# v1_0_Sensor.net
KiCad netlist of a schematic drawn in EAGLE
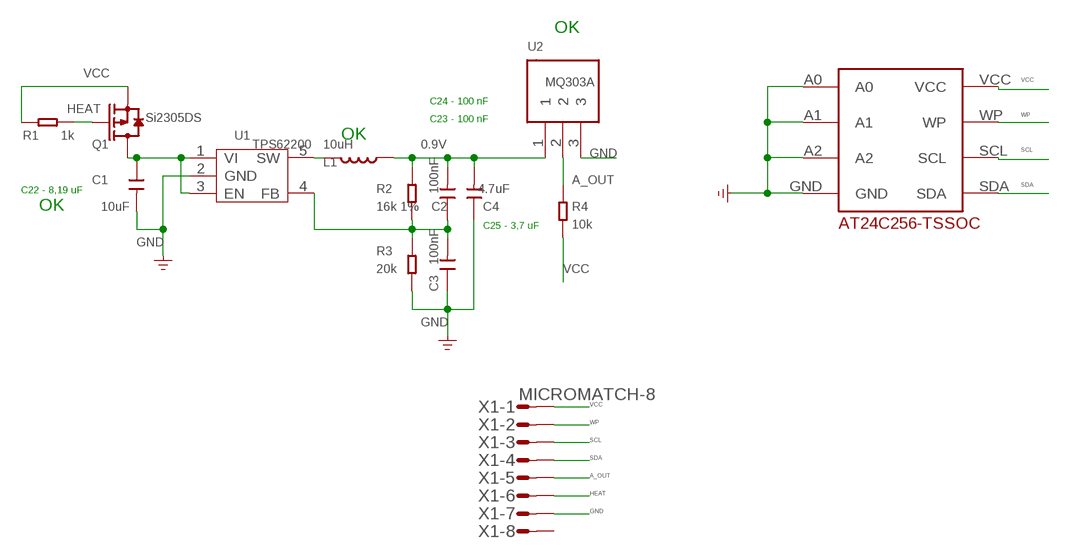
[diagram p0: schematic, sheet 1]

(export (version "E")
  (design (tool "Eeschema 10.0.6"))
  (components
    (comp (ref "C1")
      (value "10uF")
      (footprint "eagle-import:C0805")
      (libsource (lib "eagle-import") (part "C-0805"))
    )
    (comp (ref "C2")
      (value "100nF")
      (footprint "eagle-import:C0603")
      (libsource (lib "eagle-import") (part "C-0603"))
    )
    (comp (ref "C3")
      (value "100nF")
      (footprint "eagle-import:C0603")
      (libsource (lib "eagle-import") (part "C-0603"))
    )
    (comp (ref "C4")
      (value "4.7uF")
      (footprint "eagle-import:C0805")
      (libsource (lib "eagle-import") (part "C-0805"))
    )
    (comp (ref "L1")
      (value "10uH")
      (footprint "eagle-import:PIO73")
      (libsource (lib "eagle-import") (part "L'PIO73'"))
    )
    (comp (ref "Q1")
      (value "Si2305DS")
      (footprint "eagle-import:SOT23")
      (libsource (lib "eagle-import") (part "MOSFET-P'SI2323CDS/SI2305DS{lt}BR{gt}'"))
    )
    (comp (ref "R1")
      (value "1k")
      (footprint "eagle-import:R0603")
      (libsource (lib "eagle-import") (part "R-0603"))
    )
    (comp (ref "R2")
      (value "16k 1%")
      (footprint "eagle-import:R0603")
      (libsource (lib "eagle-import") (part "R-0603"))
    )
    (comp (ref "R3")
      (value "20k")
      (footprint "eagle-import:R0603")
      (libsource (lib "eagle-import") (part "R-0603"))
    )
    (comp (ref "R4")
      (value "10k")
      (footprint "eagle-import:R0603")
      (libsource (lib "eagle-import") (part "R-0603"))
    )
    (comp (ref "U$1")
      (value "DECADE-AT24C256-10TI-2.7")
      (footprint "eagle-import:DECADE-AT24CXX")
      (libsource (lib "eagle-import") (part "DECADE-AT24C256-10TI-2.7"))
    )
    (comp (ref "U1")
      (value "TPS62200")
      (footprint "eagle-import:SOT23-5")
      (libsource (lib "eagle-import") (part "TPS62200DBV"))
    )
    (comp (ref "U2")
      (value "MQ303A")
      (footprint "eagle-import:MQ303A")
      (libsource (lib "eagle-import") (part "MQ303A"))
    )
    (comp (ref "X1")
      (value "MICROMATCH-8")
      (footprint "eagle-import:MICROMATCH-8")
      (fields (field (name "MF") "FARNELL") (field (name "MPN") "7-215464-8"))
      (libsource (lib "eagle-import") (part "MICROMATCH-8"))
    )
  )
  (nets
    (net (code "1") (name "/0.9V") (class "Default")
      (node (ref "C2") (pin "2") (pinfunction "2_2") (pintype "passive"))
      (node (ref "C4") (pin "2") (pinfunction "2_2") (pintype "passive"))
      (node (ref "L1") (pin "2") (pinfunction "2_2") (pintype "passive"))
      (node (ref "R2") (pin "1") (pinfunction "1_1") (pintype "passive"))
      (node (ref "U2") (pin "1") (pinfunction "1_1") (pintype "bidirectional"))
    )
    (net (code "2") (name "/A_OUT") (class "Default")
      (node (ref "R4") (pin "1") (pinfunction "1_1") (pintype "passive"))
      (node (ref "U2") (pin "2") (pinfunction "2_2") (pintype "bidirectional"))
      (node (ref "X1") (pin "5") (pinfunction "S_5") (pintype "passive"))
    )
    (net (code "3") (name "/HEAT") (class "Default")
      (node (ref "Q1") (pin "1") (pinfunction "G_1") (pintype "passive"))
      (node (ref "R1") (pin "1") (pinfunction "1_1") (pintype "passive"))
      (node (ref "X1") (pin "6") (pinfunction "S_6") (pintype "passive"))
    )
    (net (code "4") (name "/SCL") (class "Default")
      (node (ref "U$1") (pin "SCL") (pinfunction "SCL_SCL") (pintype "bidirectional"))
      (node (ref "X1") (pin "3") (pinfunction "S_3") (pintype "passive"))
    )
    (net (code "5") (name "/SDA") (class "Default")
      (node (ref "U$1") (pin "SDA") (pinfunction "SDA_SDA") (pintype "bidirectional"))
      (node (ref "X1") (pin "4") (pinfunction "S_4") (pintype "passive"))
    )
    (net (code "6") (name "/VCC") (class "Default")
      (node (ref "Q1") (pin "2") (pinfunction "S_2") (pintype "passive"))
      (node (ref "R1") (pin "2") (pinfunction "2_2") (pintype "passive"))
      (node (ref "R4") (pin "2") (pinfunction "2_2") (pintype "passive"))
      (node (ref "U$1") (pin "VCC") (pinfunction "VCC_VCC") (pintype "bidirectional"))
      (node (ref "X1") (pin "1") (pinfunction "S_1") (pintype "passive"))
    )
    (net (code "7") (name "/WP") (class "Default")
      (node (ref "U$1") (pin "WP") (pinfunction "WP_WP") (pintype "bidirectional"))
      (node (ref "X1") (pin "2") (pinfunction "S_2") (pintype "passive"))
    )
    (net (code "8") (name "GND_POWER") (class "Default")
      (node (ref "C1") (pin "2") (pinfunction "2_2") (pintype "passive"))
      (node (ref "C3") (pin "1") (pinfunction "1_1") (pintype "passive"))
      (node (ref "C4") (pin "1") (pinfunction "1_1") (pintype "passive"))
      (node (ref "R3") (pin "2") (pinfunction "2_2") (pintype "passive"))
      (node (ref "U$1") (pin "A0") (pinfunction "A0_A0") (pintype "bidirectional"))
      (node (ref "U$1") (pin "A1") (pinfunction "A1_A1") (pintype "bidirectional"))
      (node (ref "U$1") (pin "A2") (pinfunction "A2_A2") (pintype "bidirectional"))
      (node (ref "U$1") (pin "GND") (pinfunction "GND_GND") (pintype "bidirectional"))
      (node (ref "U1") (pin "2") (pinfunction "GND_2") (pintype "power_in"))
      (node (ref "U2") (pin "3") (pinfunction "3_3") (pintype "bidirectional"))
      (node (ref "X1") (pin "7") (pinfunction "S_7") (pintype "passive"))
    )
    (net (code "9") (name "Net-(Q1-D)") (class "Default")
      (node (ref "C1") (pin "1") (pinfunction "1_1") (pintype "passive"))
      (node (ref "Q1") (pin "3") (pinfunction "D_3") (pintype "passive"))
      (node (ref "U1") (pin "1") (pinfunction "VI_1") (pintype "input"))
      (node (ref "U1") (pin "3") (pinfunction "EN_3") (pintype "input"))
    )
    (net (code "10") (name "Net-(U1-FB)") (class "Default")
      (node (ref "C2") (pin "1") (pinfunction "1_1") (pintype "passive"))
      (node (ref "C3") (pin "2") (pinfunction "2_2") (pintype "passive"))
      (node (ref "R2") (pin "2") (pinfunction "2_2") (pintype "passive"))
      (node (ref "R3") (pin "1") (pinfunction "1_1") (pintype "passive"))
      (node (ref "U1") (pin "4") (pinfunction "FB_4") (pintype "input"))
    )
    (net (code "11") (name "Net-(U1-SW)") (class "Default")
      (node (ref "L1") (pin "1") (pinfunction "1_1") (pintype "passive"))
      (node (ref "U1") (pin "5") (pinfunction "SW_5") (pintype "bidirectional"))
    )
    (net (code "12") (name "unconnected-(X1H-S-Pad8)") (class "Default")
      (node (ref "X1") (pin "8") (pinfunction "S_8") (pintype "passive"))
    )
  )
)
